# JSerial2g.net
KiCad netlist of a schematic drawn in EAGLE
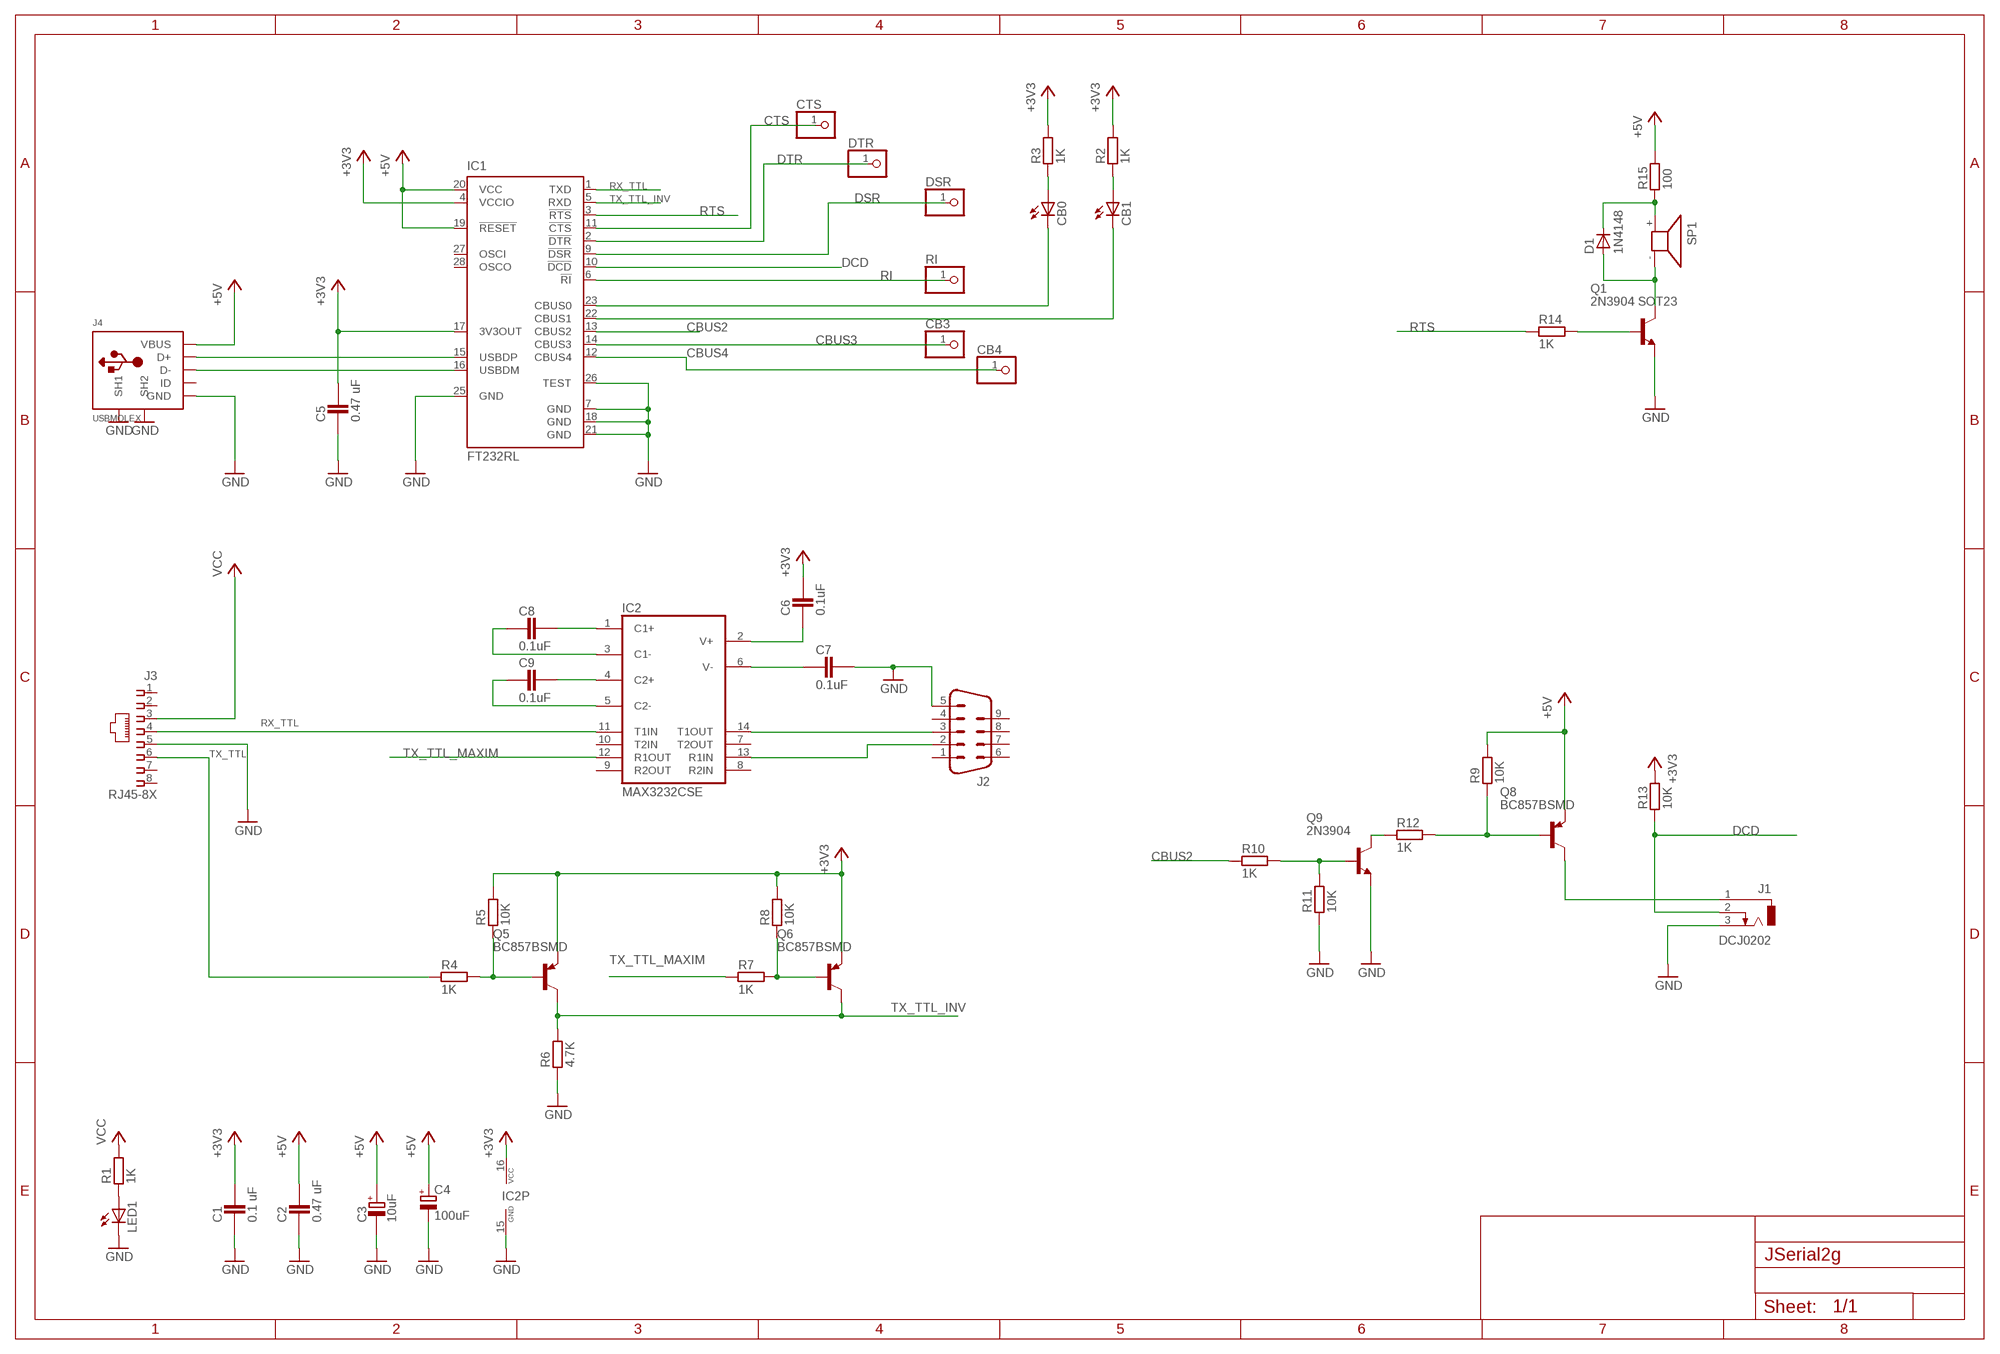
[diagram p0: schematic, sheet 1]

(export (version "E")
  (design (tool "Eeschema 10.0.6"))
  (components
    (comp (ref "C1")
      (value "0.1 uF")
      (footprint "eagle-import:CAPC2012X145AN")
      (libsource (lib "eagle-import") (part "CAPACITOR_0805"))
    )
    (comp (ref "C2")
      (value "0.47 uF")
      (footprint "eagle-import:CAPC2012X145AN")
      (libsource (lib "eagle-import") (part "CAPACITOR_0805"))
    )
    (comp (ref "C3")
      (value "10uF")
      (footprint "eagle-import:CAPMP3216X180N")
      (libsource (lib "eagle-import") (part "POLARISED_A_CASE"))
    )
    (comp (ref "C4")
      (value "100uF")
      (footprint "eagle-import:E2,5-6")
      (libsource (lib "eagle-import") (part "CPOL-EUE2.5-6"))
    )
    (comp (ref "C5")
      (value "0.47 uF")
      (footprint "eagle-import:CAPC2012X145AN")
      (libsource (lib "eagle-import") (part "CAPACITOR_0805"))
    )
    (comp (ref "C6")
      (value "0.1uF")
      (footprint "eagle-import:CAPC2012X145AN")
      (libsource (lib "eagle-import") (part "CAPACITOR_0805"))
    )
    (comp (ref "C7")
      (value "0.1uF")
      (footprint "eagle-import:CAPC2012X145AN")
      (libsource (lib "eagle-import") (part "CAPACITOR_0805"))
    )
    (comp (ref "C8")
      (value "0.1uF")
      (footprint "eagle-import:CAPC2012X145AN")
      (libsource (lib "eagle-import") (part "CAPACITOR_0805"))
    )
    (comp (ref "C9")
      (value "0.1uF")
      (footprint "eagle-import:CAPC2012X145AN")
      (libsource (lib "eagle-import") (part "CAPACITOR_0805"))
    )
    (comp (ref "CB0")
      (value "LED3MM")
      (footprint "eagle-import:LED3MM")
      (libsource (lib "eagle-import") (part "LED3MM"))
    )
    (comp (ref "CB1")
      (value "LED3MM")
      (footprint "eagle-import:LED3MM")
      (libsource (lib "eagle-import") (part "LED3MM"))
    )
    (comp (ref "CB3")
      (value "PINHD-1X1")
      (footprint "eagle-import:1X01")
      (libsource (lib "eagle-import") (part "PINHD-1X1"))
    )
    (comp (ref "CB4")
      (value "PINHD-1X1")
      (footprint "eagle-import:1X01")
      (libsource (lib "eagle-import") (part "PINHD-1X1"))
    )
    (comp (ref "CTS")
      (value "PINHD-1X1")
      (footprint "eagle-import:1X01")
      (libsource (lib "eagle-import") (part "PINHD-1X1"))
    )
    (comp (ref "D1")
      (value "1N4148")
      (footprint "eagle-import:SOD3718X135N")
      (libsource (lib "eagle-import") (part "DIODE_SOD-123"))
    )
    (comp (ref "DSR")
      (value "PINHD-1X1")
      (footprint "eagle-import:1X01")
      (libsource (lib "eagle-import") (part "PINHD-1X1"))
    )
    (comp (ref "DTR")
      (value "PINHD-1X1")
      (footprint "eagle-import:1X01")
      (libsource (lib "eagle-import") (part "PINHD-1X1"))
    )
    (comp (ref "IC1")
      (value "FT232RL")
      (footprint "eagle-import:SSOP28")
      (libsource (lib "eagle-import") (part "FT232RL"))
    )
    (comp (ref "IC2")
      (value "MAX3232CSE")
      (footprint "eagle-import:SO16")
      (libsource (lib "eagle-import") (part "MAX3232SEC"))
    )
    (comp (ref "J1")
      (value "DCJ0202")
      (footprint "eagle-import:DCJ0202")
      (libsource (lib "eagle-import") (part "DCJ0202"))
    )
    (comp (ref "J2")
      (value "M09D")
      (footprint "eagle-import:M09D")
      (libsource (lib "eagle-import") (part "M09D"))
    )
    (comp (ref "J3")
      (value "RJ45-8X")
      (footprint "eagle-import:RJ45-NO-SHIELD")
      (libsource (lib "eagle-import") (part "RJ45-8X"))
    )
    (comp (ref "J4")
      (value "USBMOLEX")
      (footprint "eagle-import:HW-MU-5F-20")
      (libsource (lib "eagle-import") (part "USBMOLEX"))
    )
    (comp (ref "LED1")
      (value "LED3MM")
      (footprint "eagle-import:LED3MM")
      (libsource (lib "eagle-import") (part "LED3MM"))
    )
    (comp (ref "Q1")
      (value "2N3904 SOT23")
      (footprint "eagle-import:SOT95P280X135-3N")
      (libsource (lib "eagle-import") (part "NPN_SOT-23"))
    )
    (comp (ref "Q5")
      (value "BC857BSMD")
      (footprint "eagle-import:SOT23-BEC")
      (libsource (lib "eagle-import") (part "BC857SMDB"))
    )
    (comp (ref "Q6")
      (value "BC857BSMD")
      (footprint "eagle-import:SOT23-BEC")
      (libsource (lib "eagle-import") (part "BC857SMDB"))
    )
    (comp (ref "Q8")
      (value "BC857BSMD")
      (footprint "eagle-import:SOT23-BEC")
      (libsource (lib "eagle-import") (part "BC857SMDB"))
    )
    (comp (ref "Q9")
      (value "2N3904")
      (footprint "eagle-import:SOT95P280X135-3N")
      (libsource (lib "eagle-import") (part "NPN_SOT-23"))
    )
    (comp (ref "R1")
      (value "1K")
      (footprint "eagle-import:RESC2012X70N")
      (libsource (lib "eagle-import") (part "RESISTOR_0805"))
    )
    (comp (ref "R2")
      (value "1K")
      (footprint "eagle-import:RESC2012X70N")
      (libsource (lib "eagle-import") (part "RESISTOR_0805"))
    )
    (comp (ref "R3")
      (value "1K")
      (footprint "eagle-import:RESC2012X70N")
      (libsource (lib "eagle-import") (part "RESISTOR_0805"))
    )
    (comp (ref "R4")
      (value "1K")
      (footprint "eagle-import:RESC2012X70N")
      (libsource (lib "eagle-import") (part "RESISTOR_0805"))
    )
    (comp (ref "R5")
      (value "10K")
      (footprint "eagle-import:RESC2012X70N")
      (libsource (lib "eagle-import") (part "RESISTOR_0805"))
    )
    (comp (ref "R6")
      (value "4.7K")
      (footprint "eagle-import:RESC2012X70N")
      (libsource (lib "eagle-import") (part "RESISTOR_0805"))
    )
    (comp (ref "R7")
      (value "1K")
      (footprint "eagle-import:RESC2012X70N")
      (libsource (lib "eagle-import") (part "RESISTOR_0805"))
    )
    (comp (ref "R8")
      (value "10K")
      (footprint "eagle-import:RESC2012X70N")
      (libsource (lib "eagle-import") (part "RESISTOR_0805"))
    )
    (comp (ref "R9")
      (value "10K")
      (footprint "eagle-import:RESC2012X70N")
      (libsource (lib "eagle-import") (part "RESISTOR_0805"))
    )
    (comp (ref "R10")
      (value "1K")
      (footprint "eagle-import:RESC2012X70N")
      (libsource (lib "eagle-import") (part "RESISTOR_0805"))
    )
    (comp (ref "R11")
      (value "10K")
      (footprint "eagle-import:RESC2012X70N")
      (libsource (lib "eagle-import") (part "RESISTOR_0805"))
    )
    (comp (ref "R12")
      (value "1K")
      (footprint "eagle-import:RESC2012X70N")
      (libsource (lib "eagle-import") (part "RESISTOR_0805"))
    )
    (comp (ref "R13")
      (value "10K")
      (footprint "eagle-import:RESC2012X70N")
      (libsource (lib "eagle-import") (part "RESISTOR_0805"))
    )
    (comp (ref "R14")
      (value "1K")
      (footprint "eagle-import:RESC2012X70N")
      (libsource (lib "eagle-import") (part "RESISTOR_0805"))
    )
    (comp (ref "R15")
      (value "100")
      (footprint "eagle-import:RESC2012X70N")
      (libsource (lib "eagle-import") (part "RESISTOR_0805"))
    )
    (comp (ref "RI")
      (value "PINHD-1X1")
      (footprint "eagle-import:1X01")
      (libsource (lib "eagle-import") (part "PINHD-1X1"))
    )
    (comp (ref "SP1")
      (value "KSS1201")
      (footprint "eagle-import:KSS1201")
      (libsource (lib "eagle-import") (part "KSS1201"))
    )
  )
  (nets
    (net (code "1") (name "+3V3") (class "Default")
      (node (ref "C1") (pin "2") (pinfunction "2_2") (pintype "passive"))
      (node (ref "C5") (pin "2") (pinfunction "2_2") (pintype "passive"))
      (node (ref "C6") (pin "2") (pinfunction "2_2") (pintype "passive"))
      (node (ref "IC1") (pin "17") (pinfunction "3V3OUT_17") (pintype "power_in"))
      (node (ref "IC1") (pin "4") (pinfunction "VCCIO_4") (pintype "power_in"))
      (node (ref "IC2") (pin "16") (pinfunction "VCC_16") (pintype "power_in"))
      (node (ref "Q5") (pin "E") (pinfunction "E_E") (pintype "passive"))
      (node (ref "Q6") (pin "E") (pinfunction "E_E") (pintype "passive"))
      (node (ref "R13") (pin "2") (pinfunction "2_2") (pintype "passive"))
      (node (ref "R2") (pin "2") (pinfunction "2_2") (pintype "passive"))
      (node (ref "R3") (pin "2") (pinfunction "2_2") (pintype "passive"))
      (node (ref "R5") (pin "2") (pinfunction "2_2") (pintype "passive"))
      (node (ref "R8") (pin "2") (pinfunction "2_2") (pintype "passive"))
    )
    (net (code "2") (name "+5V") (class "Default")
      (node (ref "C2") (pin "2") (pinfunction "2_2") (pintype "passive"))
      (node (ref "C3") (pin "+") (pinfunction "+_+") (pintype "passive"))
      (node (ref "C4") (pin "+") (pinfunction "+_+") (pintype "passive"))
      (node (ref "IC1") (pin "19") (pinfunction "~{RESET}_19") (pintype "input"))
      (node (ref "IC1") (pin "20") (pinfunction "VCC_20") (pintype "power_in"))
      (node (ref "J4") (pin "VBUS") (pinfunction "VBUS_VBUS") (pintype "power_in"))
      (node (ref "Q8") (pin "E") (pinfunction "E_E") (pintype "passive"))
      (node (ref "R15") (pin "2") (pinfunction "2_2") (pintype "passive"))
      (node (ref "R9") (pin "2") (pinfunction "2_2") (pintype "passive"))
    )
    (net (code "3") (name "/CBUS2") (class "Default")
      (node (ref "IC1") (pin "13") (pinfunction "CBUS2_13") (pintype "bidirectional"))
      (node (ref "R10") (pin "1") (pinfunction "1_1") (pintype "passive"))
    )
    (net (code "4") (name "/CBUS3") (class "Default")
      (node (ref "CB3") (pin "1") (pinfunction "1_1") (pintype "passive"))
      (node (ref "IC1") (pin "14") (pinfunction "CBUS3_14") (pintype "bidirectional"))
    )
    (net (code "5") (name "/CBUS4") (class "Default")
      (node (ref "CB4") (pin "1") (pinfunction "1_1") (pintype "passive"))
      (node (ref "IC1") (pin "12") (pinfunction "CBUS4_12") (pintype "bidirectional"))
    )
    (net (code "6") (name "/CTS") (class "Default")
      (node (ref "CTS") (pin "1") (pinfunction "1_1") (pintype "passive"))
      (node (ref "IC1") (pin "11") (pinfunction "~{CTS}_11") (pintype "input"))
    )
    (net (code "7") (name "/DCD") (class "Default")
      (node (ref "IC1") (pin "10") (pinfunction "~{DCD}_10") (pintype "input"))
      (node (ref "J1") (pin "2") (pinfunction "2_2") (pintype "passive"))
      (node (ref "R13") (pin "1") (pinfunction "1_1") (pintype "passive"))
    )
    (net (code "8") (name "/DSR") (class "Default")
      (node (ref "DSR") (pin "1") (pinfunction "1_1") (pintype "passive"))
      (node (ref "IC1") (pin "9") (pinfunction "~{DSR}_9") (pintype "input"))
    )
    (net (code "9") (name "/DTR") (class "Default")
      (node (ref "DTR") (pin "1") (pinfunction "1_1") (pintype "passive"))
      (node (ref "IC1") (pin "2") (pinfunction "~{DTR}_2") (pintype "output"))
    )
    (net (code "10") (name "/RI") (class "Default")
      (node (ref "IC1") (pin "6") (pinfunction "~{RI}_6") (pintype "input"))
      (node (ref "RI") (pin "1") (pinfunction "1_1") (pintype "passive"))
    )
    (net (code "11") (name "/RTS") (class "Default")
      (node (ref "IC1") (pin "3") (pinfunction "~{RTS}_3") (pintype "output"))
      (node (ref "R14") (pin "1") (pinfunction "1_1") (pintype "passive"))
    )
    (net (code "12") (name "/RX_TTL") (class "Default")
      (node (ref "IC1") (pin "1") (pinfunction "TXD_1") (pintype "output"))
      (node (ref "IC2") (pin "11") (pinfunction "T1IN_11") (pintype "input"))
      (node (ref "J3") (pin "4") (pinfunction "4_4") (pintype "passive"))
    )
    (net (code "13") (name "/TX_TTL") (class "Default")
      (node (ref "J3") (pin "6") (pinfunction "6_6") (pintype "passive"))
      (node (ref "R4") (pin "1") (pinfunction "1_1") (pintype "passive"))
    )
    (net (code "14") (name "/TX_TTL_INV") (class "Default")
      (node (ref "IC1") (pin "5") (pinfunction "RXD_5") (pintype "input"))
      (node (ref "Q5") (pin "C") (pinfunction "C_C") (pintype "passive"))
      (node (ref "Q6") (pin "C") (pinfunction "C_C") (pintype "passive"))
      (node (ref "R6") (pin "2") (pinfunction "2_2") (pintype "passive"))
    )
    (net (code "15") (name "/TX_TTL_MAXIM") (class "Default")
      (node (ref "IC2") (pin "12") (pinfunction "R1OUT_12") (pintype "output"))
      (node (ref "R7") (pin "1") (pinfunction "1_1") (pintype "passive"))
    )
    (net (code "16") (name "GND") (class "Default")
      (node (ref "C1") (pin "1") (pinfunction "1_1") (pintype "passive"))
      (node (ref "C2") (pin "1") (pinfunction "1_1") (pintype "passive"))
      (node (ref "C3") (pin "-") (pinfunction "-_-") (pintype "passive"))
      (node (ref "C4") (pin "-") (pinfunction "-_-") (pintype "passive"))
      (node (ref "C5") (pin "1") (pinfunction "1_1") (pintype "passive"))
      (node (ref "C7") (pin "2") (pinfunction "2_2") (pintype "passive"))
      (node (ref "IC1") (pin "18") (pinfunction "GND_18") (pintype "power_in"))
      (node (ref "IC1") (pin "21") (pinfunction "GND_21") (pintype "power_in"))
      (node (ref "IC1") (pin "25") (pinfunction "GND_25") (pintype "power_in"))
      (node (ref "IC1") (pin "26") (pinfunction "TEST_26") (pintype "input"))
      (node (ref "IC1") (pin "7") (pinfunction "GND_7") (pintype "power_in"))
      (node (ref "IC2") (pin "15") (pinfunction "GND_15") (pintype "power_in"))
      (node (ref "J1") (pin "3") (pinfunction "3_3") (pintype "passive"))
      (node (ref "J2") (pin "5") (pinfunction "5_5") (pintype "passive"))
      (node (ref "J3") (pin "5") (pinfunction "5_5") (pintype "passive"))
      (node (ref "J4") (pin "GND") (pinfunction "GND_GND") (pintype "power_in"))
      (node (ref "J4") (pin "SH1") (pinfunction "SH1_SH1") (pintype "power_in"))
      (node (ref "J4") (pin "SH2") (pinfunction "SH2_SH2") (pintype "power_in"))
      (node (ref "LED1") (pin "K") (pinfunction "C_K") (pintype "passive"))
      (node (ref "Q1") (pin "2") (pinfunction "E_2") (pintype "passive"))
      (node (ref "Q9") (pin "2") (pinfunction "E_2") (pintype "passive"))
      (node (ref "R11") (pin "1") (pinfunction "1_1") (pintype "passive"))
      (node (ref "R6") (pin "1") (pinfunction "1_1") (pintype "passive"))
    )
    (net (code "17") (name "Net-(CB0-C)") (class "Default")
      (node (ref "CB0") (pin "K") (pinfunction "C_K") (pintype "passive"))
      (node (ref "IC1") (pin "23") (pinfunction "CBUS0_23") (pintype "bidirectional"))
    )
    (net (code "18") (name "Net-(CB0-PadA)") (class "Default")
      (node (ref "CB0") (pin "A") (pinfunction "A_A") (pintype "passive"))
      (node (ref "R3") (pin "1") (pinfunction "1_1") (pintype "passive"))
    )
    (net (code "19") (name "Net-(CB1-C)") (class "Default")
      (node (ref "CB1") (pin "K") (pinfunction "C_K") (pintype "passive"))
      (node (ref "IC1") (pin "22") (pinfunction "CBUS1_22") (pintype "bidirectional"))
    )
    (net (code "20") (name "Net-(CB1-PadA)") (class "Default")
      (node (ref "CB1") (pin "A") (pinfunction "A_A") (pintype "passive"))
      (node (ref "R2") (pin "1") (pinfunction "1_1") (pintype "passive"))
    )
    (net (code "21") (name "Net-(IC1-USBDM)") (class "Default")
      (node (ref "IC1") (pin "16") (pinfunction "USBDM_16") (pintype "bidirectional"))
      (node (ref "J4") (pin "D-") (pinfunction "D-_D-") (pintype "bidirectional"))
    )
    (net (code "22") (name "Net-(IC1-USBDP)") (class "Default")
      (node (ref "IC1") (pin "15") (pinfunction "USBDP_15") (pintype "bidirectional"))
      (node (ref "J4") (pin "D+") (pinfunction "D+_D+") (pintype "bidirectional"))
    )
    (net (code "23") (name "Net-(IC2A-C1+)") (class "Default")
      (node (ref "C8") (pin "2") (pinfunction "2_2") (pintype "passive"))
      (node (ref "IC2") (pin "1") (pinfunction "C1+_1") (pintype "bidirectional"))
    )
    (net (code "24") (name "Net-(IC2A-C1-)") (class "Default")
      (node (ref "C8") (pin "1") (pinfunction "1_1") (pintype "passive"))
      (node (ref "IC2") (pin "3") (pinfunction "C1-_3") (pintype "bidirectional"))
    )
    (net (code "25") (name "Net-(IC2A-C2+)") (class "Default")
      (node (ref "C9") (pin "2") (pinfunction "2_2") (pintype "passive"))
      (node (ref "IC2") (pin "4") (pinfunction "C2+_4") (pintype "bidirectional"))
    )
    (net (code "26") (name "Net-(IC2A-C2-)") (class "Default")
      (node (ref "C9") (pin "1") (pinfunction "1_1") (pintype "passive"))
      (node (ref "IC2") (pin "5") (pinfunction "C2-_5") (pintype "bidirectional"))
    )
    (net (code "27") (name "Net-(IC2A-R1IN)") (class "Default")
      (node (ref "IC2") (pin "13") (pinfunction "R1IN_13") (pintype "input"))
      (node (ref "J2") (pin "2") (pinfunction "2_2") (pintype "passive"))
    )
    (net (code "28") (name "Net-(IC2A-T1OUT)") (class "Default")
      (node (ref "IC2") (pin "14") (pinfunction "T1OUT_14") (pintype "output"))
      (node (ref "J2") (pin "3") (pinfunction "3_3") (pintype "passive"))
    )
    (net (code "29") (name "Net-(IC2A-V+)") (class "Default")
      (node (ref "C6") (pin "1") (pinfunction "1_1") (pintype "passive"))
      (node (ref "IC2") (pin "2") (pinfunction "V+_2") (pintype "bidirectional"))
    )
    (net (code "30") (name "Net-(IC2A-V-)") (class "Default")
      (node (ref "C7") (pin "1") (pinfunction "1_1") (pintype "passive"))
      (node (ref "IC2") (pin "6") (pinfunction "V-_6") (pintype "bidirectional"))
    )
    (net (code "31") (name "Net-(J1-Pad1)") (class "Default")
      (node (ref "J1") (pin "1") (pinfunction "1_1") (pintype "passive"))
      (node (ref "Q8") (pin "C") (pinfunction "C_C") (pintype "passive"))
    )
    (net (code "32") (name "Net-(LED1-PadA)") (class "Default")
      (node (ref "LED1") (pin "A") (pinfunction "A_A") (pintype "passive"))
      (node (ref "R1") (pin "1") (pinfunction "1_1") (pintype "passive"))
    )
    (net (code "33") (name "Net-(Q1-B)") (class "Default")
      (node (ref "Q1") (pin "1") (pinfunction "B_1") (pintype "passive"))
      (node (ref "R14") (pin "2") (pinfunction "2_2") (pintype "passive"))
    )
    (net (code "34") (name "Net-(Q1-C)") (class "Default")
      (node (ref "D1") (pin "A") (pinfunction "A_A") (pintype "passive"))
      (node (ref "Q1") (pin "3") (pinfunction "C_3") (pintype "passive"))
      (node (ref "SP1") (pin "-") (pinfunction "2_-") (pintype "passive"))
    )
    (net (code "35") (name "Net-(Q5-PadB)") (class "Default")
      (node (ref "Q5") (pin "B") (pinfunction "B_B") (pintype "passive"))
      (node (ref "R4") (pin "2") (pinfunction "2_2") (pintype "passive"))
      (node (ref "R5") (pin "1") (pinfunction "1_1") (pintype "passive"))
    )
    (net (code "36") (name "Net-(Q6-PadB)") (class "Default")
      (node (ref "Q6") (pin "B") (pinfunction "B_B") (pintype "passive"))
      (node (ref "R7") (pin "2") (pinfunction "2_2") (pintype "passive"))
      (node (ref "R8") (pin "1") (pinfunction "1_1") (pintype "passive"))
    )
    (net (code "37") (name "Net-(Q8-PadB)") (class "Default")
      (node (ref "Q8") (pin "B") (pinfunction "B_B") (pintype "passive"))
      (node (ref "R12") (pin "2") (pinfunction "2_2") (pintype "passive"))
      (node (ref "R9") (pin "1") (pinfunction "1_1") (pintype "passive"))
    )
    (net (code "38") (name "Net-(Q9-B)") (class "Default")
      (node (ref "Q9") (pin "1") (pinfunction "B_1") (pintype "passive"))
      (node (ref "R10") (pin "2") (pinfunction "2_2") (pintype "passive"))
      (node (ref "R11") (pin "2") (pinfunction "2_2") (pintype "passive"))
    )
    (net (code "39") (name "Net-(Q9-C)") (class "Default")
      (node (ref "Q9") (pin "3") (pinfunction "C_3") (pintype "passive"))
      (node (ref "R12") (pin "1") (pinfunction "1_1") (pintype "passive"))
    )
    (net (code "40") (name "Net-(SP1-1)") (class "Default")
      (node (ref "D1") (pin "K") (pinfunction "K_K") (pintype "passive"))
      (node (ref "R15") (pin "1") (pinfunction "1_1") (pintype "passive"))
      (node (ref "SP1") (pin "+") (pinfunction "1_+") (pintype "passive"))
    )
    (net (code "41") (name "VCC") (class "Default")
      (node (ref "J3") (pin "3") (pinfunction "3_3") (pintype "passive"))
      (node (ref "R1") (pin "2") (pinfunction "2_2") (pintype "passive"))
    )
    (net (code "42") (name "unconnected-(IC1-OSCI-Pad27)") (class "Default")
      (node (ref "IC1") (pin "27") (pinfunction "OSCI_27") (pintype "input"))
    )
    (net (code "43") (name "unconnected-(IC1-OSCO-Pad28)") (class "Default")
      (node (ref "IC1") (pin "28") (pinfunction "OSCO_28") (pintype "output"))
    )
    (net (code "44") (name "unconnected-(IC2A-R2IN-Pad8)") (class "Default")
      (node (ref "IC2") (pin "8") (pinfunction "R2IN_8") (pintype "input"))
    )
    (net (code "45") (name "unconnected-(IC2A-R2OUT-Pad9)") (class "Default")
      (node (ref "IC2") (pin "9") (pinfunction "R2OUT_9") (pintype "output"))
    )
    (net (code "46") (name "unconnected-(IC2A-T2IN-Pad10)") (class "Default")
      (node (ref "IC2") (pin "10") (pinfunction "T2IN_10") (pintype "input"))
    )
    (net (code "47") (name "unconnected-(IC2A-T2OUT-Pad7)") (class "Default")
      (node (ref "IC2") (pin "7") (pinfunction "T2OUT_7") (pintype "output"))
    )
    (net (code "48") (name "unconnected-(J2-Pad1)") (class "Default")
      (node (ref "J2") (pin "1") (pinfunction "1_1") (pintype "passive"))
    )
    (net (code "49") (name "unconnected-(J2-Pad4)") (class "Default")
      (node (ref "J2") (pin "4") (pinfunction "4_4") (pintype "passive"))
    )
    (net (code "50") (name "unconnected-(J2-Pad6)") (class "Default")
      (node (ref "J2") (pin "6") (pinfunction "6_6") (pintype "passive"))
    )
    (net (code "51") (name "unconnected-(J2-Pad7)") (class "Default")
      (node (ref "J2") (pin "7") (pinfunction "7_7") (pintype "passive"))
    )
    (net (code "52") (name "unconnected-(J2-Pad8)") (class "Default")
      (node (ref "J2") (pin "8") (pinfunction "8_8") (pintype "passive"))
    )
    (net (code "53") (name "unconnected-(J2-Pad9)") (class "Default")
      (node (ref "J2") (pin "9") (pinfunction "9_9") (pintype "passive"))
    )
    (net (code "54") (name "unconnected-(J3-Pad1)") (class "Default")
      (node (ref "J3") (pin "1") (pinfunction "1_1") (pintype "passive"))
    )
    (net (code "55") (name "unconnected-(J3-Pad2)") (class "Default")
      (node (ref "J3") (pin "2") (pinfunction "2_2") (pintype "passive"))
    )
    (net (code "56") (name "unconnected-(J3-Pad7)") (class "Default")
      (node (ref "J3") (pin "7") (pinfunction "7_7") (pintype "passive"))
    )
    (net (code "57") (name "unconnected-(J3-Pad8)") (class "Default")
      (node (ref "J3") (pin "8") (pinfunction "8_8") (pintype "passive"))
    )
    (net (code "58") (name "unconnected-(J4-PadID)") (class "Default")
      (node (ref "J4") (pin "ID") (pinfunction "ID_ID") (pintype "bidirectional"))
    )
  )
)
